# ADC_GPIO_Expander.net
KiCad netlist of a schematic drawn in Altium Designer
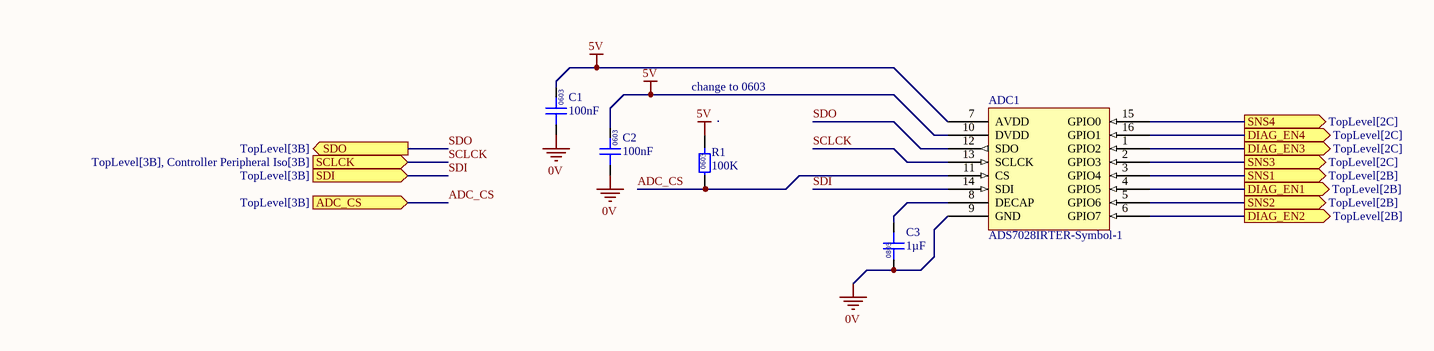
[diagram p0: ADC GPIO Expander.SchDoc]

(export (version "E")
  (design (tool "Eeschema 10.0.6"))
  (components
    (comp (ref "ADC1")
      (value "ADS7028IRTER-Symbol-1")
      (footprint "WFQN-16")
      (description "IC ADC 12BIT SAR 16WQFN")
      (fields (field (name "PART NUMBER") "ADS7028IRTER") (field (name "MANUFACTURER") "Texas Instruments"))
      (libsource (lib "ts_standard_library") (part "ADS7028IRTER"))
    )
    (comp (ref "C1")
      (value "100nF")
      (footprint "0603")
      (fields
        (field (name "PART NUMBER") "GCM188L81H104KA57D")
        (field (name "MANUFACTURER") "muRata")
        (field (name "TOLERANCE") "±10%")
      )
      (libsource (lib "ts_standard_library") (part "Capacitor 0603"))
    )
    (comp (ref "C2")
      (value "100nF")
      (footprint "0603")
      (fields
        (field (name "PART NUMBER") "GCM188L81H104KA57D")
        (field (name "MANUFACTURER") "muRata")
        (field (name "TOLERANCE") "±10%")
      )
      (libsource (lib "ts_standard_library") (part "Capacitor 0603"))
    )
    (comp (ref "C3")
      (value "1µF")
      (footprint "0805")
      (fields
        (field (name "PART NUMBER") "GCM21BR71H105KA03L")
        (field (name "MANUFACTURER") "muRata")
        (field (name "TOLERANCE") "±10%")
      )
      (libsource (lib "ts_standard_library") (part "Capacitor 0805"))
    )
    (comp (ref "R1")
      (value "100K")
      (footprint "0603")
      (fields
        (field (name "PART NUMBER") "RC0603FR-07100KL")
        (field (name "MANUFACTURER") "YAGEO")
        (field (name "TOLERANCE") "0.01")
      )
      (libsource (lib "ts_standard_library") (part "Resistor 0603"))
    )
  )
  (nets
    (net (code "1") (name "/ADC_CS") (class "Default")
      (node (ref "ADC1") (pin "11") (pinfunction "CS_11") (pintype "input"))
      (node (ref "R1") (pin "1") (pinfunction "1_1") (pintype "passive"))
    )
    (net (code "2") (name "/DIAG_EN1") (class "Default")
      (node (ref "ADC1") (pin "4") (pinfunction "GPIO5_4") (pintype "input"))
    )
    (net (code "3") (name "/DIAG_EN2") (class "Default")
      (node (ref "ADC1") (pin "6") (pinfunction "GPIO7_6") (pintype "input"))
    )
    (net (code "4") (name "/DIAG_EN3") (class "Default")
      (node (ref "ADC1") (pin "1") (pinfunction "GPIO2_1") (pintype "input"))
    )
    (net (code "5") (name "/DIAG_EN4") (class "Default")
      (node (ref "ADC1") (pin "16") (pinfunction "GPIO1_16") (pintype "input"))
    )
    (net (code "6") (name "/SCLCK") (class "Default")
      (node (ref "ADC1") (pin "13") (pinfunction "SCLCK_13") (pintype "input"))
    )
    (net (code "7") (name "/SDI") (class "Default")
      (node (ref "ADC1") (pin "14") (pinfunction "SDI_14") (pintype "input"))
    )
    (net (code "8") (name "/SDO") (class "Default")
      (node (ref "ADC1") (pin "12") (pinfunction "SDO_12") (pintype "output"))
    )
    (net (code "9") (name "/SNS1") (class "Default")
      (node (ref "ADC1") (pin "3") (pinfunction "GPIO4_3") (pintype "input"))
    )
    (net (code "10") (name "/SNS2") (class "Default")
      (node (ref "ADC1") (pin "5") (pinfunction "GPIO6_5") (pintype "input"))
    )
    (net (code "11") (name "/SNS3") (class "Default")
      (node (ref "ADC1") (pin "2") (pinfunction "GPIO3_2") (pintype "input"))
    )
    (net (code "12") (name "/SNS4") (class "Default")
      (node (ref "ADC1") (pin "15") (pinfunction "GPIO0_15") (pintype "input"))
    )
    (net (code "13") (name "0V") (class "Default")
      (node (ref "ADC1") (pin "9") (pinfunction "GND_9") (pintype "power_in"))
      (node (ref "C1") (pin "1") (pinfunction "1_1") (pintype "passive"))
      (node (ref "C2") (pin "1") (pinfunction "1_1") (pintype "passive"))
      (node (ref "C3") (pin "1") (pinfunction "1_1") (pintype "passive"))
    )
    (net (code "14") (name "5V") (class "Default")
      (node (ref "ADC1") (pin "10") (pinfunction "DVDD_10") (pintype "power_in"))
      (node (ref "ADC1") (pin "7") (pinfunction "AVDD_7") (pintype "power_in"))
      (node (ref "C1") (pin "2") (pinfunction "2_2") (pintype "passive"))
      (node (ref "C2") (pin "2") (pinfunction "2_2") (pintype "passive"))
      (node (ref "R1") (pin "2") (pinfunction "2_2") (pintype "passive"))
    )
    (net (code "15") (name "Net-(ADC1-DECAP)") (class "Default")
      (node (ref "ADC1") (pin "8") (pinfunction "DECAP_8") (pintype "power_in"))
      (node (ref "C3") (pin "2") (pinfunction "2_2") (pintype "passive"))
    )
  )
)
